# Enclosure_Front_NusbioPlus.net
KiCad netlist of a schematic drawn in EAGLE
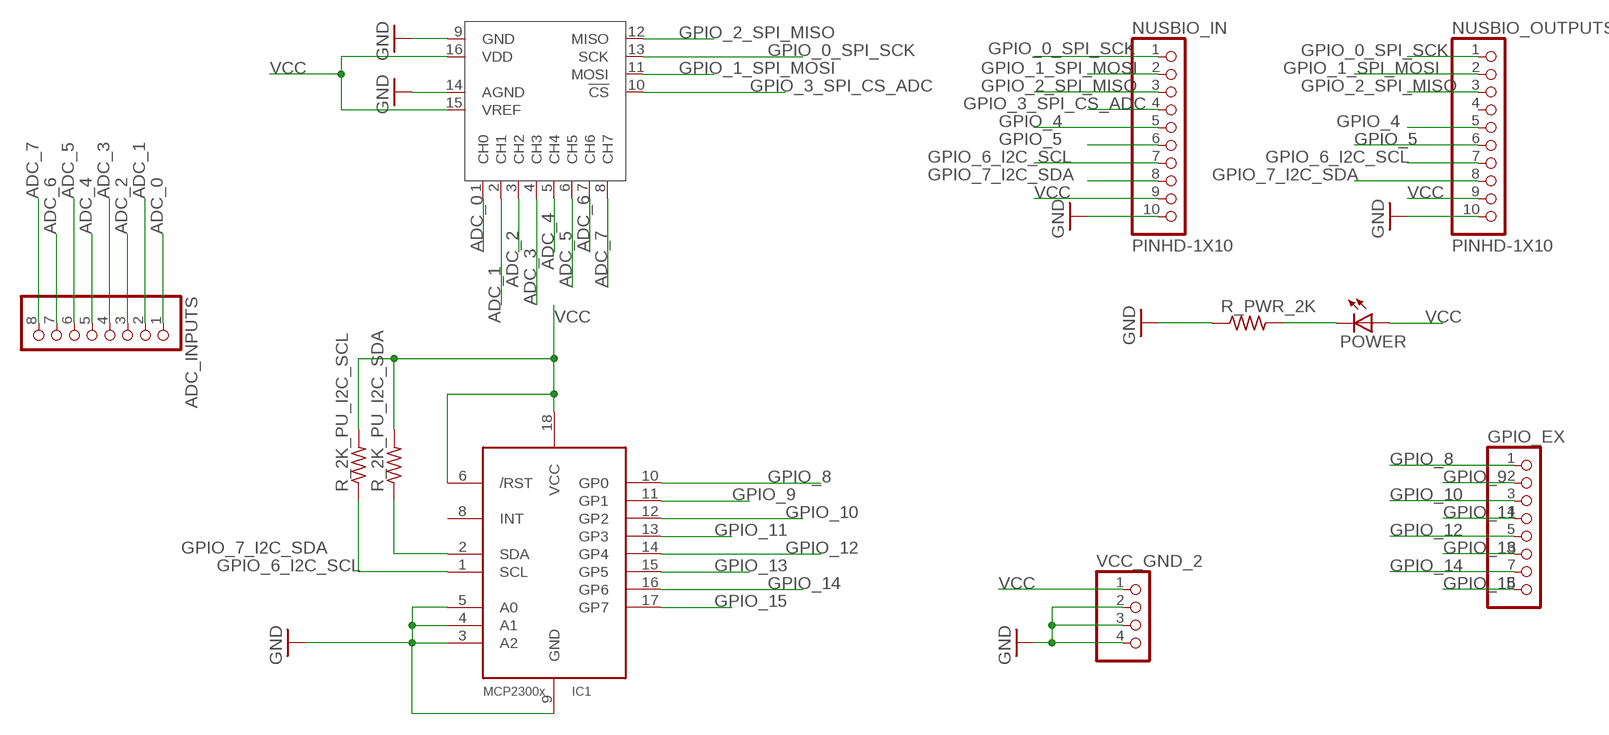
[diagram p0: schematic, sheet 1]

(export (version "E")
  (design (tool "Eeschema 10.0.6"))
  (components
    (comp (ref "ADC_INPUTS")
      (value "PINHD-1X8")
      (footprint "eagle-import:1X08")
      (libsource (lib "eagle-import") (part "PINHD-1X8"))
    )
    (comp (ref "GPIO_EX")
      (value "PINHD-1X8")
      (footprint "eagle-import:1X08")
      (libsource (lib "eagle-import") (part "PINHD-1X8"))
    )
    (comp (ref "IC1")
      (value "MCP23008/SO")
      (footprint "eagle-import:SO18W")
      (libsource (lib "eagle-import") (part "MCP23008/SO"))
    )
    (comp (ref "NUSBIO_IN")
      (value "PINHD-1X10")
      (footprint "eagle-import:1X10-BIG")
      (libsource (lib "eagle-import") (part "PINHD-1X10"))
    )
    (comp (ref "NUSBIO_OUTPUTS")
      (value "PINHD-1X10")
      (footprint "eagle-import:1X10-BIG")
      (libsource (lib "eagle-import") (part "PINHD-1X10"))
    )
    (comp (ref "POWER")
      (value "LEDSMT1206")
      (footprint "eagle-import:1206")
      (libsource (lib "eagle-import") (part "LEDSMT1206"))
    )
    (comp (ref "R_2K_PU_I2C_SCL")
      (value "R-US_R1206")
      (footprint "eagle-import:R1206")
      (libsource (lib "eagle-import") (part "R-US_R1206"))
    )
    (comp (ref "R_2K_PU_I2C_SDA")
      (value "R-US_R1206")
      (footprint "eagle-import:R1206")
      (libsource (lib "eagle-import") (part "R-US_R1206"))
    )
    (comp (ref "R_PWR_2K")
      (value "R-US_R1206")
      (footprint "eagle-import:R1206")
      (libsource (lib "eagle-import") (part "R-US_R1206"))
    )
    (comp (ref "U$1")
      (value "MCP3008SL")
      (footprint "eagle-import:SO16")
      (libsource (lib "eagle-import") (part "MCP3008SL"))
    )
    (comp (ref "VCC_GND_2")
      (value "PINHD-1X4")
      (footprint "eagle-import:1X04")
      (libsource (lib "eagle-import") (part "PINHD-1X4"))
    )
  )
  (nets
    (net (code "1") (name "/ADC_0") (class "Default")
      (node (ref "ADC_INPUTS") (pin "1") (pinfunction "1_1") (pintype "passive"))
      (node (ref "U$1") (pin "1") (pinfunction "CH0_1") (pintype "input"))
    )
    (net (code "2") (name "/ADC_1") (class "Default")
      (node (ref "ADC_INPUTS") (pin "2") (pinfunction "2_2") (pintype "passive"))
      (node (ref "U$1") (pin "2") (pinfunction "CH1_2") (pintype "input"))
    )
    (net (code "3") (name "/ADC_2") (class "Default")
      (node (ref "ADC_INPUTS") (pin "3") (pinfunction "3_3") (pintype "passive"))
      (node (ref "U$1") (pin "3") (pinfunction "CH2_3") (pintype "input"))
    )
    (net (code "4") (name "/ADC_3") (class "Default")
      (node (ref "ADC_INPUTS") (pin "4") (pinfunction "4_4") (pintype "passive"))
      (node (ref "U$1") (pin "4") (pinfunction "CH3_4") (pintype "input"))
    )
    (net (code "5") (name "/ADC_4") (class "Default")
      (node (ref "ADC_INPUTS") (pin "5") (pinfunction "5_5") (pintype "passive"))
      (node (ref "U$1") (pin "5") (pinfunction "CH4_5") (pintype "input"))
    )
    (net (code "6") (name "/ADC_5") (class "Default")
      (node (ref "ADC_INPUTS") (pin "6") (pinfunction "6_6") (pintype "passive"))
      (node (ref "U$1") (pin "6") (pinfunction "CH5_6") (pintype "input"))
    )
    (net (code "7") (name "/ADC_6") (class "Default")
      (node (ref "ADC_INPUTS") (pin "7") (pinfunction "7_7") (pintype "passive"))
      (node (ref "U$1") (pin "7") (pinfunction "CH6_7") (pintype "input"))
    )
    (net (code "8") (name "/ADC_7") (class "Default")
      (node (ref "ADC_INPUTS") (pin "8") (pinfunction "8_8") (pintype "passive"))
      (node (ref "U$1") (pin "8") (pinfunction "CH7_8") (pintype "input"))
    )
    (net (code "9") (name "/GPIO_0_SPI_SCK") (class "Default")
      (node (ref "NUSBIO_IN") (pin "1") (pinfunction "1_1") (pintype "passive"))
      (node (ref "NUSBIO_OUTPUTS") (pin "1") (pinfunction "1_1") (pintype "passive"))
      (node (ref "U$1") (pin "13") (pinfunction "SCK_13") (pintype "input"))
    )
    (net (code "10") (name "/GPIO_1_SPI_MOSI") (class "Default")
      (node (ref "NUSBIO_IN") (pin "2") (pinfunction "2_2") (pintype "passive"))
      (node (ref "NUSBIO_OUTPUTS") (pin "2") (pinfunction "2_2") (pintype "passive"))
      (node (ref "U$1") (pin "11") (pinfunction "MOSI_11") (pintype "input"))
    )
    (net (code "11") (name "/GPIO_2_SPI_MISO") (class "Default")
      (node (ref "NUSBIO_IN") (pin "3") (pinfunction "3_3") (pintype "passive"))
      (node (ref "NUSBIO_OUTPUTS") (pin "3") (pinfunction "3_3") (pintype "passive"))
      (node (ref "U$1") (pin "12") (pinfunction "MISO_12") (pintype "output"))
    )
    (net (code "12") (name "/GPIO_3_SPI_CS_ADC") (class "Default")
      (node (ref "NUSBIO_IN") (pin "4") (pinfunction "4_4") (pintype "passive"))
      (node (ref "U$1") (pin "10") (pinfunction "~{CS}_10") (pintype "input"))
    )
    (net (code "13") (name "/GPIO_4") (class "Default")
      (node (ref "NUSBIO_IN") (pin "5") (pinfunction "5_5") (pintype "passive"))
      (node (ref "NUSBIO_OUTPUTS") (pin "5") (pinfunction "5_5") (pintype "passive"))
    )
    (net (code "14") (name "/GPIO_5") (class "Default")
      (node (ref "NUSBIO_IN") (pin "6") (pinfunction "6_6") (pintype "passive"))
      (node (ref "NUSBIO_OUTPUTS") (pin "6") (pinfunction "6_6") (pintype "passive"))
    )
    (net (code "15") (name "/GPIO_6_I2C_SCL") (class "Default")
      (node (ref "IC1") (pin "1") (pinfunction "SCL_1") (pintype "bidirectional"))
      (node (ref "NUSBIO_IN") (pin "7") (pinfunction "7_7") (pintype "passive"))
      (node (ref "NUSBIO_OUTPUTS") (pin "7") (pinfunction "7_7") (pintype "passive"))
      (node (ref "R_2K_PU_I2C_SCL") (pin "1") (pinfunction "1_1") (pintype "passive"))
    )
    (net (code "16") (name "/GPIO_7_I2C_SDA") (class "Default")
      (node (ref "IC1") (pin "2") (pinfunction "SDA_2") (pintype "bidirectional"))
      (node (ref "NUSBIO_IN") (pin "8") (pinfunction "8_8") (pintype "passive"))
      (node (ref "NUSBIO_OUTPUTS") (pin "8") (pinfunction "8_8") (pintype "passive"))
      (node (ref "R_2K_PU_I2C_SDA") (pin "1") (pinfunction "1_1") (pintype "passive"))
    )
    (net (code "17") (name "/GPIO_8") (class "Default")
      (node (ref "GPIO_EX") (pin "1") (pinfunction "1_1") (pintype "passive"))
      (node (ref "IC1") (pin "10") (pinfunction "GP0_10") (pintype "bidirectional"))
    )
    (net (code "18") (name "/GPIO_9") (class "Default")
      (node (ref "GPIO_EX") (pin "2") (pinfunction "2_2") (pintype "passive"))
      (node (ref "IC1") (pin "11") (pinfunction "GP1_11") (pintype "bidirectional"))
    )
    (net (code "19") (name "/GPIO_10") (class "Default")
      (node (ref "GPIO_EX") (pin "3") (pinfunction "3_3") (pintype "passive"))
      (node (ref "IC1") (pin "12") (pinfunction "GP2_12") (pintype "bidirectional"))
    )
    (net (code "20") (name "/GPIO_11") (class "Default")
      (node (ref "GPIO_EX") (pin "4") (pinfunction "4_4") (pintype "passive"))
      (node (ref "IC1") (pin "13") (pinfunction "GP3_13") (pintype "bidirectional"))
    )
    (net (code "21") (name "/GPIO_12") (class "Default")
      (node (ref "GPIO_EX") (pin "5") (pinfunction "5_5") (pintype "passive"))
      (node (ref "IC1") (pin "14") (pinfunction "GP4_14") (pintype "bidirectional"))
    )
    (net (code "22") (name "/GPIO_13") (class "Default")
      (node (ref "GPIO_EX") (pin "6") (pinfunction "6_6") (pintype "passive"))
      (node (ref "IC1") (pin "15") (pinfunction "GP5_15") (pintype "bidirectional"))
    )
    (net (code "23") (name "/GPIO_14") (class "Default")
      (node (ref "GPIO_EX") (pin "7") (pinfunction "7_7") (pintype "passive"))
      (node (ref "IC1") (pin "16") (pinfunction "GP6_16") (pintype "bidirectional"))
    )
    (net (code "24") (name "/GPIO_15") (class "Default")
      (node (ref "GPIO_EX") (pin "8") (pinfunction "8_8") (pintype "passive"))
      (node (ref "IC1") (pin "17") (pinfunction "GP7_17") (pintype "bidirectional"))
    )
    (net (code "25") (name "/VCC") (class "Default")
      (node (ref "IC1") (pin "18") (pinfunction "VCC_18") (pintype "power_in"))
      (node (ref "IC1") (pin "6") (pinfunction "/RST_6") (pintype "input"))
      (node (ref "NUSBIO_IN") (pin "9") (pinfunction "9_9") (pintype "passive"))
      (node (ref "NUSBIO_OUTPUTS") (pin "9") (pinfunction "9_9") (pintype "passive"))
      (node (ref "POWER") (pin "A") (pinfunction "A_A") (pintype "passive"))
      (node (ref "R_2K_PU_I2C_SCL") (pin "2") (pinfunction "2_2") (pintype "passive"))
      (node (ref "R_2K_PU_I2C_SDA") (pin "2") (pinfunction "2_2") (pintype "passive"))
      (node (ref "U$1") (pin "15") (pinfunction "VREF_15") (pintype "power_in"))
      (node (ref "U$1") (pin "16") (pinfunction "VDD_16") (pintype "power_in"))
      (node (ref "VCC_GND_2") (pin "1") (pinfunction "1_1") (pintype "passive"))
    )
    (net (code "26") (name "GND") (class "Default")
      (node (ref "IC1") (pin "3") (pinfunction "A2_3") (pintype "input"))
      (node (ref "IC1") (pin "4") (pinfunction "A1_4") (pintype "input"))
      (node (ref "IC1") (pin "5") (pinfunction "A0_5") (pintype "input"))
      (node (ref "IC1") (pin "9") (pinfunction "GND_9") (pintype "power_in"))
      (node (ref "NUSBIO_IN") (pin "10") (pinfunction "10_10") (pintype "passive"))
      (node (ref "NUSBIO_OUTPUTS") (pin "10") (pinfunction "10_10") (pintype "passive"))
      (node (ref "R_PWR_2K") (pin "1") (pinfunction "1_1") (pintype "passive"))
      (node (ref "U$1") (pin "14") (pinfunction "AGND_14") (pintype "power_in"))
      (node (ref "U$1") (pin "9") (pinfunction "GND_9") (pintype "power_in"))
      (node (ref "VCC_GND_2") (pin "2") (pinfunction "2_2") (pintype "passive"))
      (node (ref "VCC_GND_2") (pin "3") (pinfunction "3_3") (pintype "passive"))
      (node (ref "VCC_GND_2") (pin "4") (pinfunction "4_4") (pintype "passive"))
    )
    (net (code "27") (name "Net-(POWER-PadC)") (class "Default")
      (node (ref "POWER") (pin "C") (pinfunction "C_C") (pintype "passive"))
      (node (ref "R_PWR_2K") (pin "2") (pinfunction "2_2") (pintype "passive"))
    )
    (net (code "28") (name "unconnected-(IC1-INT-Pad8)") (class "Default")
      (node (ref "IC1") (pin "8") (pinfunction "INT_8") (pintype "output"))
    )
    (net (code "29") (name "unconnected-(NUSBIO_OUTPUTS-Pad4)") (class "Default")
      (node (ref "NUSBIO_OUTPUTS") (pin "4") (pinfunction "4_4") (pintype "passive"))
    )
  )
)
